# Motor_Driver_Schematic_2.net
KiCad netlist of a schematic drawn in Altium Designer
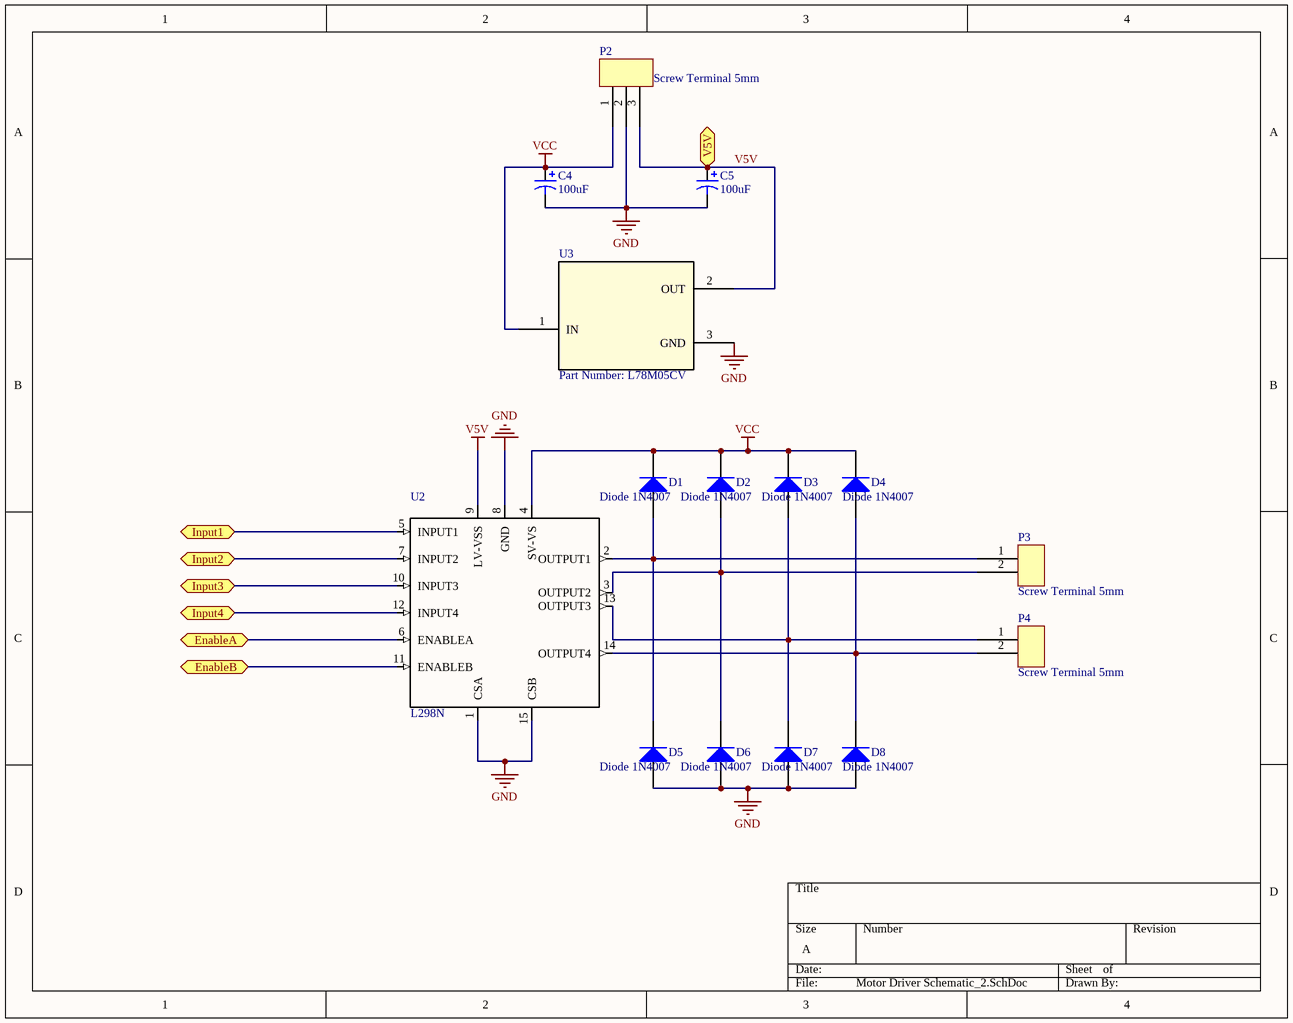
[diagram p0: Motor Driver Schematic_2.SchDoc]

(export (version "E")
  (design (tool "Eeschema 10.0.6"))
  (components
    (comp (ref "C4")
      (value "100uF")
      (footprint "RB7.6-15")
      (description "Polarized Capacitor (Radial)")
      (fields (field (name "Comment") "Cap Pol1") (field (name "PUBLISHER") "Altium Limited"))
      (libsource (lib "Miscellaneous Devices") (part "Cap Pol1"))
    )
    (comp (ref "C5")
      (value "100uF")
      (footprint "RB7.6-15")
      (description "Polarized Capacitor (Radial)")
      (fields (field (name "Comment") "Cap Pol1") (field (name "PUBLISHER") "Altium Limited"))
      (libsource (lib "Miscellaneous Devices") (part "Cap Pol1"))
    )
    (comp (ref "D1")
      (value "Diode 1N4007")
      (footprint "DO-41")
      (description "1 Amp General Purpose Rectifier")
      (fields (field (name "PUBLISHER") "Altium Limited"))
      (libsource (lib "Miscellaneous Devices") (part "Diode 1N4007"))
    )
    (comp (ref "D2")
      (value "Diode 1N4007")
      (footprint "DO-41")
      (description "1 Amp General Purpose Rectifier")
      (fields (field (name "PUBLISHER") "Altium Limited"))
      (libsource (lib "Miscellaneous Devices") (part "Diode 1N4007"))
    )
    (comp (ref "D3")
      (value "Diode 1N4007")
      (footprint "DO-41")
      (description "1 Amp General Purpose Rectifier")
      (fields (field (name "PUBLISHER") "Altium Limited"))
      (libsource (lib "Miscellaneous Devices") (part "Diode 1N4007"))
    )
    (comp (ref "D4")
      (value "Diode 1N4007")
      (footprint "DO-41")
      (description "1 Amp General Purpose Rectifier")
      (fields (field (name "PUBLISHER") "Altium Limited"))
      (libsource (lib "Miscellaneous Devices") (part "Diode 1N4007"))
    )
    (comp (ref "D5")
      (value "Diode 1N4007")
      (footprint "DO-41")
      (description "1 Amp General Purpose Rectifier")
      (fields (field (name "PUBLISHER") "Altium Limited"))
      (libsource (lib "Miscellaneous Devices") (part "Diode 1N4007"))
    )
    (comp (ref "D6")
      (value "Diode 1N4007")
      (footprint "DO-41")
      (description "1 Amp General Purpose Rectifier")
      (fields (field (name "PUBLISHER") "Altium Limited"))
      (libsource (lib "Miscellaneous Devices") (part "Diode 1N4007"))
    )
    (comp (ref "D7")
      (value "Diode 1N4007")
      (footprint "DO-41")
      (description "1 Amp General Purpose Rectifier")
      (fields (field (name "PUBLISHER") "Altium Limited"))
      (libsource (lib "Miscellaneous Devices") (part "Diode 1N4007"))
    )
    (comp (ref "D8")
      (value "Diode 1N4007")
      (footprint "DO-41")
      (description "1 Amp General Purpose Rectifier")
      (fields (field (name "PUBLISHER") "Altium Limited"))
      (libsource (lib "Miscellaneous Devices") (part "Diode 1N4007"))
    )
    (comp (ref "P2")
      (value "Screw Terminal 5mm")
      (footprint "PCBComponent_1")
      (description "Screw Terminal 5mm 3 pin")
      (libsource (lib "Screw_Terminal_5mm_3-pin") (part "Screw Terminal 5mm 3pin"))
    )
    (comp (ref "P3")
      (value "Screw Terminal 5mm")
      (footprint "PCBComponent_1")
      (description "Screw Terminal 5mm 2pin")
      (libsource (lib "Screw_Terminal_5mm_2pin") (part "Screw Terminal 5mm 2pin"))
    )
    (comp (ref "P4")
      (value "Screw Terminal 5mm")
      (footprint "PCBComponent_1")
      (description "Screw Terminal 5mm 2pin")
      (libsource (lib "Screw_Terminal_5mm_2pin") (part "Screw Terminal 5mm 2pin"))
    )
    (comp (ref "U2")
      (value "L298N")
      (footprint "DRIVER_L298N")
      (fields (field (name "MF") "STMicroelectronics"))
      (libsource (lib "L298N") (part "L298N"))
    )
    (comp (ref "U3")
      (value "Part Number: L78M05CV")
      (footprint "TO-220")
      (description "No Description Available")
      (fields
        (field (name "MANUFACTURER_PART_NUMBER") "L78M05CV")
        (field (name "COPYRIGHT") "Copyright (C) 2018 Accelerated Designs. All rights reserved")
      )
      (libsource (lib "2019-02-14_20-26-49") (part "L78M05CV"))
    )
  )
  (nets
    (net (code "1") (name "/EnableA") (class "Default")
      (node (ref "U2") (pin "6") (pinfunction "ENABLEA_6") (pintype "input"))
    )
    (net (code "2") (name "/EnableB") (class "Default")
      (node (ref "U2") (pin "11") (pinfunction "ENABLEB_11") (pintype "input"))
    )
    (net (code "3") (name "/Input1") (class "Default")
      (node (ref "U2") (pin "5") (pinfunction "INPUT1_5") (pintype "input"))
    )
    (net (code "4") (name "/Input2") (class "Default")
      (node (ref "U2") (pin "7") (pinfunction "INPUT2_7") (pintype "input"))
    )
    (net (code "5") (name "/Input3") (class "Default")
      (node (ref "U2") (pin "10") (pinfunction "INPUT3_10") (pintype "input"))
    )
    (net (code "6") (name "/Input4") (class "Default")
      (node (ref "U2") (pin "12") (pinfunction "INPUT4_12") (pintype "input"))
    )
    (net (code "7") (name "GND") (class "Default")
      (node (ref "C4") (pin "2") (pinfunction "2_2") (pintype "passive"))
      (node (ref "C5") (pin "2") (pinfunction "2_2") (pintype "passive"))
      (node (ref "D5") (pin "1") (pinfunction "A_1") (pintype "passive"))
      (node (ref "D6") (pin "1") (pinfunction "A_1") (pintype "passive"))
      (node (ref "D7") (pin "1") (pinfunction "A_1") (pintype "passive"))
      (node (ref "D8") (pin "1") (pinfunction "A_1") (pintype "passive"))
      (node (ref "P2") (pin "2") (pintype "passive"))
      (node (ref "U2") (pin "1") (pinfunction "CSA_1") (pintype "bidirectional"))
      (node (ref "U2") (pin "15") (pinfunction "CSB_15") (pintype "bidirectional"))
      (node (ref "U2") (pin "8") (pinfunction "GND_8") (pintype "passive"))
      (node (ref "U3") (pin "3") (pinfunction "GND_3") (pintype "power_in"))
    )
    (net (code "8") (name "Net-(D1-A)") (class "Default")
      (node (ref "D1") (pin "1") (pinfunction "A_1") (pintype "passive"))
      (node (ref "D5") (pin "2") (pinfunction "K_2") (pintype "passive"))
      (node (ref "P3") (pin "1") (pintype "passive"))
      (node (ref "U2") (pin "2") (pinfunction "OUTPUT1_2") (pintype "output"))
    )
    (net (code "9") (name "Net-(D2-A)") (class "Default")
      (node (ref "D2") (pin "1") (pinfunction "A_1") (pintype "passive"))
      (node (ref "D6") (pin "2") (pinfunction "K_2") (pintype "passive"))
      (node (ref "P3") (pin "2") (pintype "passive"))
      (node (ref "U2") (pin "3") (pinfunction "OUTPUT2_3") (pintype "output"))
    )
    (net (code "10") (name "Net-(D3-A)") (class "Default")
      (node (ref "D3") (pin "1") (pinfunction "A_1") (pintype "passive"))
      (node (ref "D7") (pin "2") (pinfunction "K_2") (pintype "passive"))
      (node (ref "P4") (pin "1") (pintype "passive"))
      (node (ref "U2") (pin "13") (pinfunction "OUTPUT3_13") (pintype "output"))
    )
    (net (code "11") (name "Net-(D4-A)") (class "Default")
      (node (ref "D4") (pin "1") (pinfunction "A_1") (pintype "passive"))
      (node (ref "D8") (pin "2") (pinfunction "K_2") (pintype "passive"))
      (node (ref "P4") (pin "2") (pintype "passive"))
      (node (ref "U2") (pin "14") (pinfunction "OUTPUT4_14") (pintype "output"))
    )
    (net (code "12") (name "V5V") (class "Default")
      (node (ref "C5") (pin "1") (pinfunction "1_1") (pintype "passive"))
      (node (ref "P2") (pin "3") (pintype "passive"))
      (node (ref "U2") (pin "9") (pinfunction "LV-VSS_9") (pintype "power_in"))
      (node (ref "U3") (pin "2") (pinfunction "OUT_2") (pintype "power_in"))
    )
    (net (code "13") (name "VCC") (class "Default")
      (node (ref "C4") (pin "1") (pinfunction "1_1") (pintype "passive"))
      (node (ref "D1") (pin "2") (pinfunction "K_2") (pintype "passive"))
      (node (ref "D2") (pin "2") (pinfunction "K_2") (pintype "passive"))
      (node (ref "D3") (pin "2") (pinfunction "K_2") (pintype "passive"))
      (node (ref "D4") (pin "2") (pinfunction "K_2") (pintype "passive"))
      (node (ref "P2") (pin "1") (pintype "passive"))
      (node (ref "U2") (pin "4") (pinfunction "SV-VS_4") (pintype "power_in"))
      (node (ref "U3") (pin "1") (pinfunction "IN_1") (pintype "power_in"))
    )
  )
)
